# POWER.net
KiCad netlist of a schematic drawn in Altium Designer
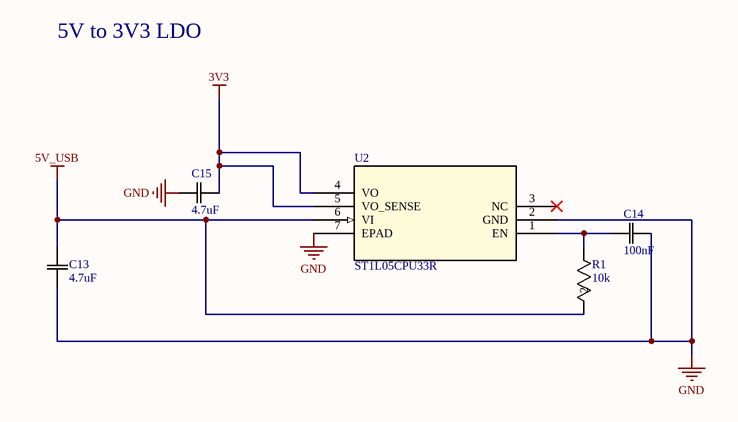
[diagram p0: POWER.SchDoc]

(export (version "E")
  (design (tool "Eeschema 10.0.6"))
  (components
    (comp (ref "C13")
      (value "4.7uF")
      (footprint "CAP_CL10_SAM")
      (description "No Description Available")
      (fields
        (field (name "MANUFACTURER_PART_NUMBER") "CL10A475MO8NNNC")
        (field (name "COPYRIGHT") "Copyright (C) 2025 Ultra Librarian. All rights reserved.")
      )
      (libsource (lib "CL10A475MO8NNNC") (part "CL10A475MO8NNNC"))
    )
    (comp (ref "C14")
      (value "100nF")
      (footprint "CAPC10555_55N_KEM")
      (description "SMD Comm X7R, Ceramic, 0.1 uF, 10%, 16 VDC, X7R, SMD, MLCC, Temperature Stable, Class II, 0402")
      (fields
        (field (name "MANUFACTURER_PART_NUMBER") "C0402C104K4RACTU")
        (field (name "COPYRIGHT") "Copyright (C) 2025 Ultra Librarian. All rights reserved.")
      )
      (libsource (lib "C0402C104K4RACTU") (part "C0402C104K4RACTU"))
    )
    (comp (ref "C15")
      (value "4.7uF")
      (footprint "LMK107_TAY")
      (description "No Description Available")
      (fields
        (field (name "MANUFACTURER_PART_NUMBER") "LMK107BJ475MAHT")
        (field (name "COPYRIGHT") "Copyright (C) 2025 Ultra Librarian. All rights reserved.")
      )
      (libsource (lib "LMK107BJ475MAHT") (part "LMK107BJ475MAHT"))
    )
    (comp (ref "R1")
      (value "10k")
      (footprint "RC0402N_YAG")
      (description "RES; SMT (0402); 10K; 1%; +/-100PPM/DEGC; 0.0630W")
      (fields
        (field (name "MANUFACTURER_PART_NUMBER") "RC0402FR-0710KL")
        (field (name "COPYRIGHT") "Copyright (C) 2025 Ultra Librarian. All rights reserved.")
      )
      (libsource (lib "RC0402FR-0710KL") (part "RC0402FR-0710KL"))
    )
    (comp (ref "U2")
      (value "ST1L05CPU33R")
      (footprint "DFN6_3X3_STM")
      (description "Very low quiescent BiCMOS voltage regulator")
      (fields (field (name "COPYRIGHT") "Copyright (C) 2025 Ultra Librarian. All rights reserved."))
      (libsource (lib "ST1L05CPU33R") (part "ST1L05CPU33R"))
    )
  )
  (nets
    (net (code "1") (name "3V3") (class "Default")
      (node (ref "C15") (pin "2") (pinfunction "2_2") (pintype "passive"))
      (node (ref "U2") (pin "4") (pinfunction "VO_4") (pintype "power_in"))
      (node (ref "U2") (pin "5") (pinfunction "VO_SENSE_5") (pintype "passive"))
    )
    (net (code "2") (name "5V_USB") (class "Default")
      (node (ref "C13") (pin "2") (pinfunction "2_2") (pintype "passive"))
      (node (ref "R1") (pin "2") (pinfunction "2_2") (pintype "passive"))
      (node (ref "U2") (pin "6") (pinfunction "VI_6") (pintype "input"))
    )
    (net (code "3") (name "GND") (class "Default")
      (node (ref "C13") (pin "1") (pinfunction "1_1") (pintype "passive"))
      (node (ref "C14") (pin "1") (pinfunction "1_1") (pintype "passive"))
      (node (ref "C15") (pin "1") (pinfunction "1_1") (pintype "passive"))
      (node (ref "U2") (pin "2") (pinfunction "GND_2") (pintype "power_in"))
      (node (ref "U2") (pin "7") (pinfunction "EPAD_7") (pintype "passive"))
    )
    (net (code "4") (name "Net-(U2-EN)") (class "Default")
      (node (ref "C14") (pin "2") (pinfunction "2_2") (pintype "passive"))
      (node (ref "R1") (pin "1") (pinfunction "1_1") (pintype "passive"))
      (node (ref "U2") (pin "1") (pinfunction "EN_1") (pintype "passive"))
    )
    (net (code "5") (name "unconnected-(U2-NC-Pad3)") (class "Default")
      (node (ref "U2") (pin "3") (pinfunction "NC_3") (pintype "passive+no_connect"))
    )
  )
)
